# 12input.net
KiCad netlist of a schematic drawn in EAGLE
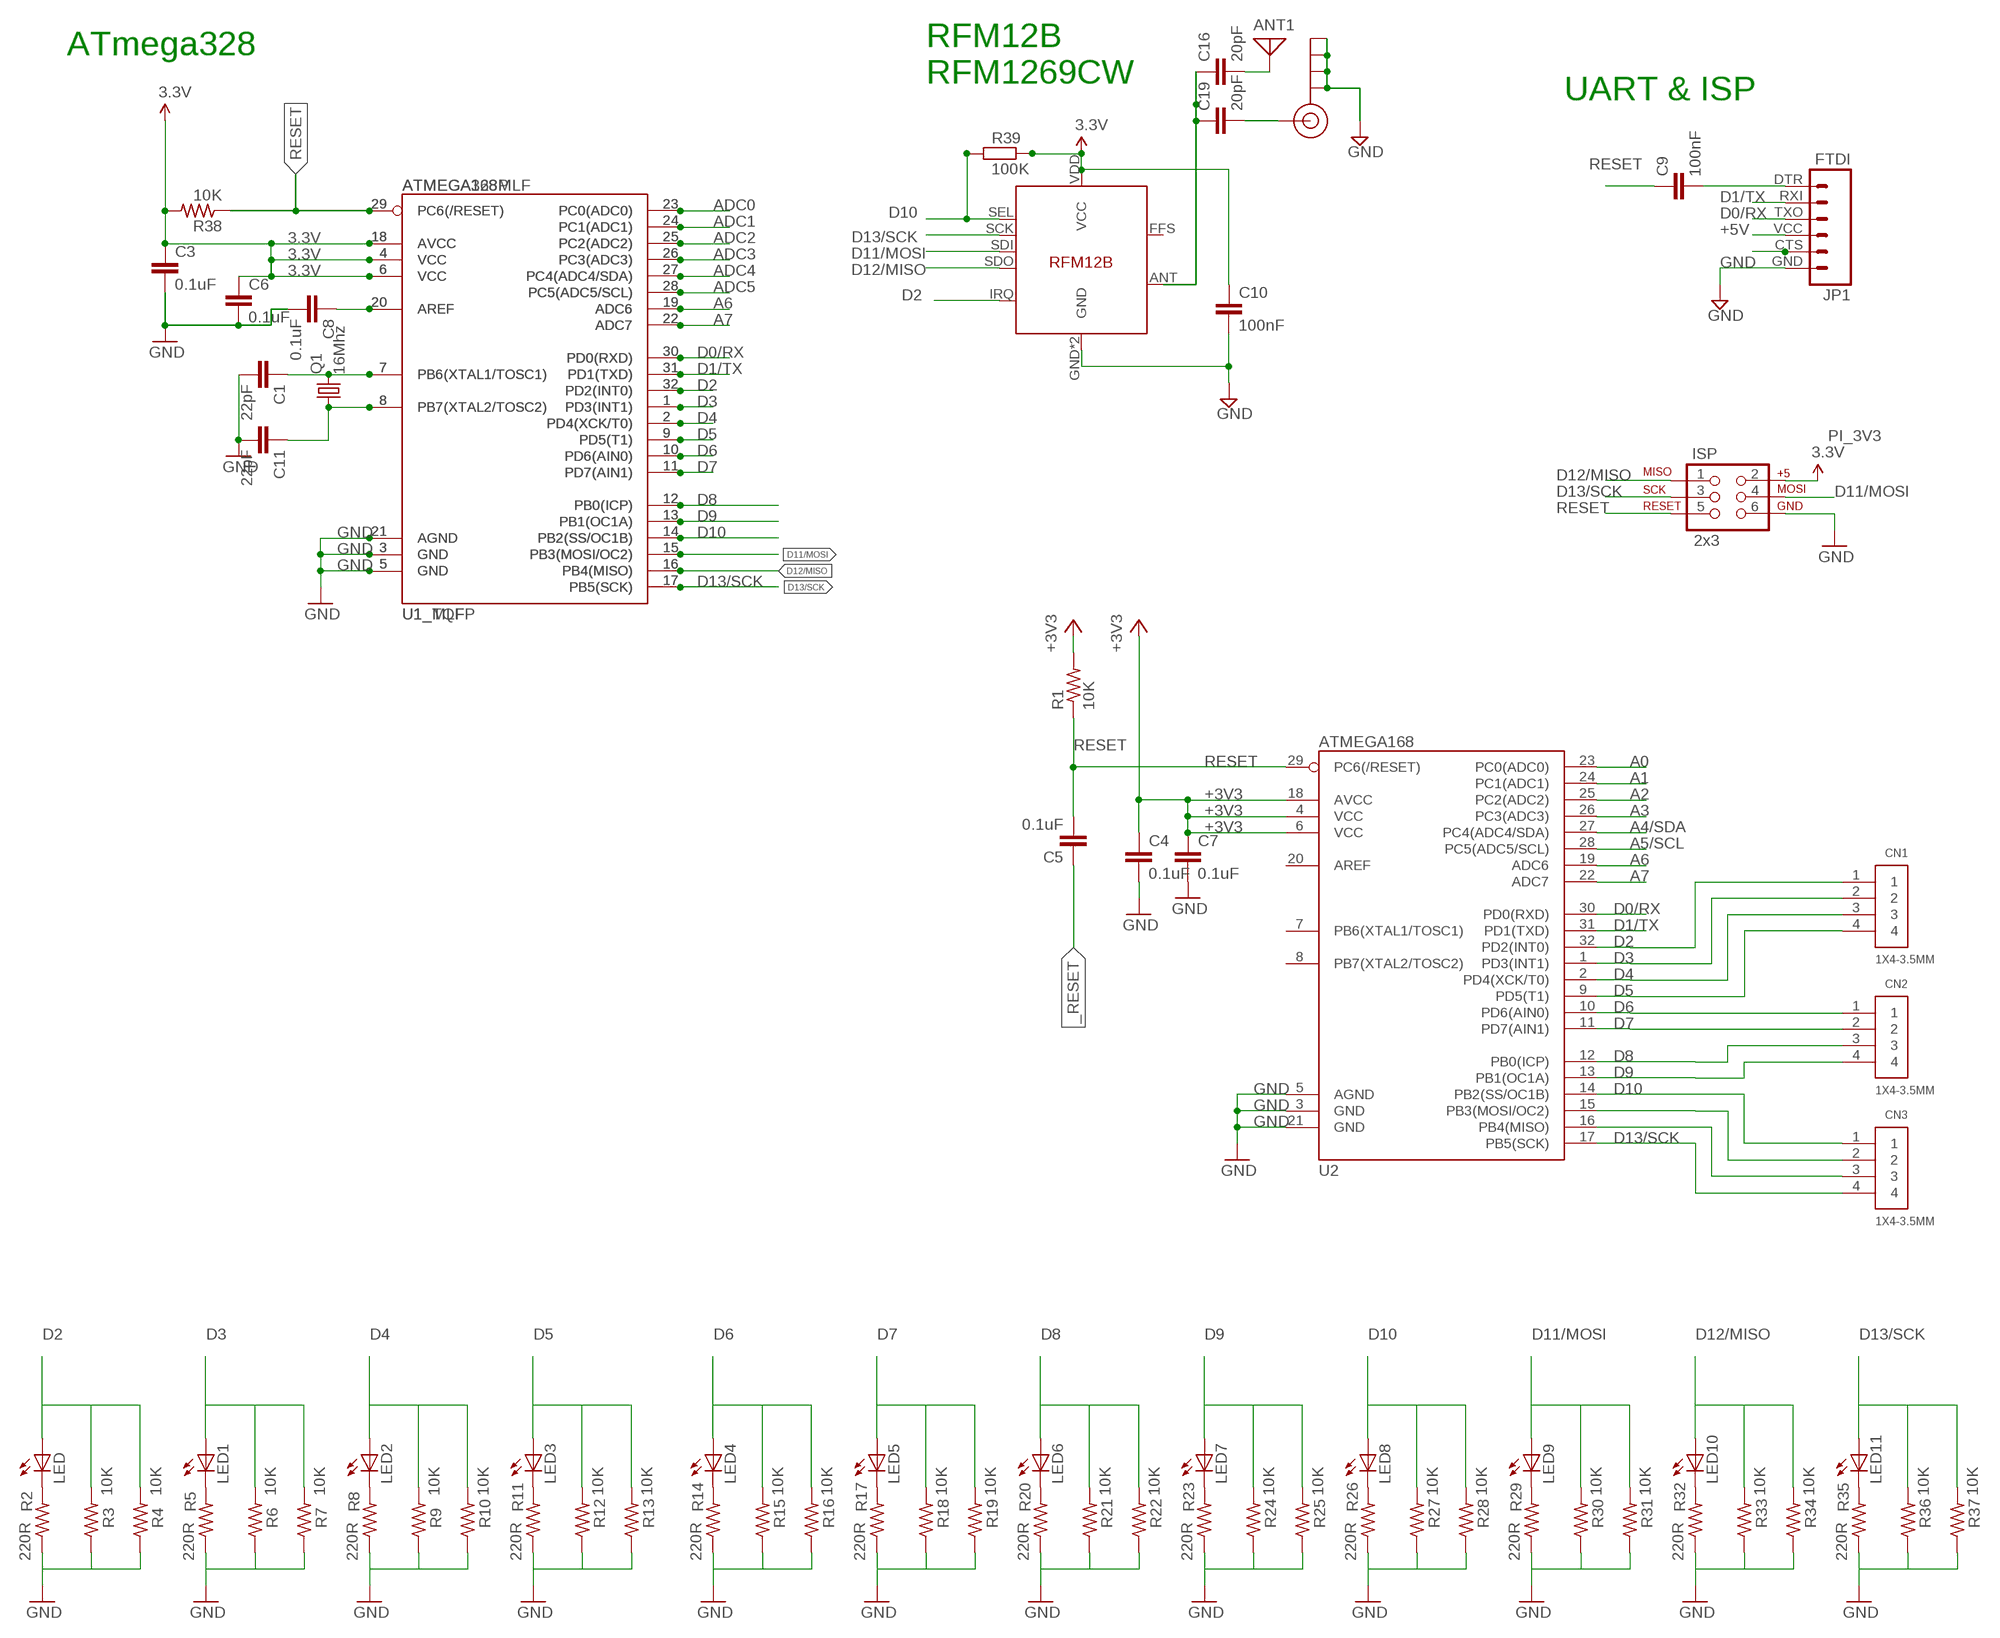
[diagram p0: schematic, sheet 1]

(export (version "E")
  (design (tool "Eeschema 10.0.6"))
  (components
    (comp (ref "ANT1")
      (value "ANTENNA")
      (footprint "eagle-import:PAD-01")
      (libsource (lib "eagle-import") (part "ANTENNA"))
    )
    (comp (ref "C1")
      (value "22pF")
      (footprint "eagle-import:C0603")
      (libsource (lib "eagle-import") (part "resistor_C-EUC0603"))
    )
    (comp (ref "C3")
      (value "0.1uF")
      (footprint "eagle-import:C0603")
      (libsource (lib "eagle-import") (part "C-EUC0603"))
    )
    (comp (ref "C4")
      (value "0.1uF")
      (footprint "eagle-import:C0603")
      (libsource (lib "eagle-import") (part "C-EUC0603"))
    )
    (comp (ref "C5")
      (value "0.1uF")
      (footprint "eagle-import:C0603")
      (libsource (lib "eagle-import") (part "C-EUC0603"))
    )
    (comp (ref "C6")
      (value "0.1uF")
      (footprint "eagle-import:C0603")
      (libsource (lib "eagle-import") (part "resistor_C-EUC0603"))
    )
    (comp (ref "C7")
      (value "0.1uF")
      (footprint "eagle-import:C0603")
      (libsource (lib "eagle-import") (part "resistor_C-EUC0603"))
    )
    (comp (ref "C8")
      (value "0.1uF")
      (footprint "eagle-import:C0603")
      (libsource (lib "eagle-import") (part "resistor_C-EUC0603"))
    )
    (comp (ref "C9")
      (value "100nF")
      (footprint "eagle-import:C0603")
      (libsource (lib "eagle-import") (part "C-EUC0603"))
    )
    (comp (ref "C10")
      (value "100nF")
      (footprint "eagle-import:C0603")
      (libsource (lib "eagle-import") (part "C-EUC0603"))
    )
    (comp (ref "C11")
      (value "22pF")
      (footprint "eagle-import:C0603")
      (libsource (lib "eagle-import") (part "resistor_C-EUC0603"))
    )
    (comp (ref "C16")
      (value "20pF")
      (footprint "eagle-import:C0603")
      (libsource (lib "eagle-import") (part "C-EUC0603"))
    )
    (comp (ref "C19")
      (value "20pF")
      (footprint "eagle-import:C0603")
      (libsource (lib "eagle-import") (part "C-EUC0603"))
    )
    (comp (ref "CN1")
      (value "1X4-3.5MM")
      (footprint "eagle-import:1X04-3.5MM")
      (libsource (lib "eagle-import") (part "1X4-3.5MM"))
    )
    (comp (ref "CN2")
      (value "1X4-3.5MM")
      (footprint "eagle-import:1X04-3.5MM")
      (libsource (lib "eagle-import") (part "1X4-3.5MM"))
    )
    (comp (ref "CN3")
      (value "1X4-3.5MM")
      (footprint "eagle-import:1X04-3.5MM")
      (libsource (lib "eagle-import") (part "1X4-3.5MM"))
    )
    (comp (ref "ISP")
      (value "2x3")
      (footprint "eagle-import:2X3")
      (libsource (lib "eagle-import") (part "AVR_SPI_PRG_6PTH"))
    )
    (comp (ref "J$1")
      (value "SMA_EDGE")
      (footprint "eagle-import:SMA-EDGE")
      (libsource (lib "eagle-import") (part "SMA_EDGE"))
    )
    (comp (ref "JP1")
      (value "FTDI")
      (footprint "eagle-import:FTDI_BASIC")
      (libsource (lib "eagle-import") (part "FTDI_BASICPTH"))
    )
    (comp (ref "LED")
      (value "LEDSML0603")
      (footprint "eagle-import:SML0603")
      (libsource (lib "eagle-import") (part "LEDSML0603"))
    )
    (comp (ref "LED1")
      (value "LEDSML0603")
      (footprint "eagle-import:SML0603")
      (libsource (lib "eagle-import") (part "LEDSML0603"))
    )
    (comp (ref "LED2")
      (value "LEDSML0603")
      (footprint "eagle-import:SML0603")
      (libsource (lib "eagle-import") (part "LEDSML0603"))
    )
    (comp (ref "LED3")
      (value "LEDSML0603")
      (footprint "eagle-import:SML0603")
      (libsource (lib "eagle-import") (part "LEDSML0603"))
    )
    (comp (ref "LED4")
      (value "LEDSML0603")
      (footprint "eagle-import:SML0603")
      (libsource (lib "eagle-import") (part "LEDSML0603"))
    )
    (comp (ref "LED5")
      (value "LEDSML0603")
      (footprint "eagle-import:SML0603")
      (libsource (lib "eagle-import") (part "LEDSML0603"))
    )
    (comp (ref "LED6")
      (value "LEDSML0603")
      (footprint "eagle-import:SML0603")
      (libsource (lib "eagle-import") (part "LEDSML0603"))
    )
    (comp (ref "LED7")
      (value "LEDSML0603")
      (footprint "eagle-import:SML0603")
      (libsource (lib "eagle-import") (part "LEDSML0603"))
    )
    (comp (ref "LED8")
      (value "LEDSML0603")
      (footprint "eagle-import:SML0603")
      (libsource (lib "eagle-import") (part "LEDSML0603"))
    )
    (comp (ref "LED9")
      (value "LEDSML0603")
      (footprint "eagle-import:SML0603")
      (libsource (lib "eagle-import") (part "LEDSML0603"))
    )
    (comp (ref "LED10")
      (value "LEDSML0603")
      (footprint "eagle-import:SML0603")
      (libsource (lib "eagle-import") (part "LEDSML0603"))
    )
    (comp (ref "LED11")
      (value "LEDSML0603")
      (footprint "eagle-import:SML0603")
      (libsource (lib "eagle-import") (part "LEDSML0603"))
    )
    (comp (ref "Q1")
      (value "16Mhz")
      (footprint "eagle-import:HC49UP")
      (libsource (lib "eagle-import") (part "CRYSTALHC49UP"))
    )
    (comp (ref "R1")
      (value "10K")
      (footprint "eagle-import:R0603")
      (libsource (lib "eagle-import") (part "R-US_R0603"))
    )
    (comp (ref "R2")
      (value "220R")
      (footprint "eagle-import:R0603")
      (libsource (lib "eagle-import") (part "R-US_R0603"))
    )
    (comp (ref "R3")
      (value "10K")
      (footprint "eagle-import:R0603")
      (libsource (lib "eagle-import") (part "R-US_R0603"))
    )
    (comp (ref "R4")
      (value "10K")
      (footprint "eagle-import:0204_7")
      (libsource (lib "eagle-import") (part "R-US_0204/7"))
    )
    (comp (ref "R5")
      (value "220R")
      (footprint "eagle-import:R0603")
      (libsource (lib "eagle-import") (part "R-US_R0603"))
    )
    (comp (ref "R6")
      (value "10K")
      (footprint "eagle-import:R0603")
      (libsource (lib "eagle-import") (part "R-US_R0603"))
    )
    (comp (ref "R7")
      (value "10K")
      (footprint "eagle-import:0204_7")
      (libsource (lib "eagle-import") (part "R-US_0204/7"))
    )
    (comp (ref "R8")
      (value "220R")
      (footprint "eagle-import:R0603")
      (libsource (lib "eagle-import") (part "R-US_R0603"))
    )
    (comp (ref "R9")
      (value "10K")
      (footprint "eagle-import:R0603")
      (libsource (lib "eagle-import") (part "R-US_R0603"))
    )
    (comp (ref "R10")
      (value "10K")
      (footprint "eagle-import:0204_7")
      (libsource (lib "eagle-import") (part "R-US_0204/7"))
    )
    (comp (ref "R11")
      (value "220R")
      (footprint "eagle-import:R0603")
      (libsource (lib "eagle-import") (part "R-US_R0603"))
    )
    (comp (ref "R12")
      (value "10K")
      (footprint "eagle-import:R0603")
      (libsource (lib "eagle-import") (part "R-US_R0603"))
    )
    (comp (ref "R13")
      (value "10K")
      (footprint "eagle-import:0204_7")
      (libsource (lib "eagle-import") (part "R-US_0204/7"))
    )
    (comp (ref "R14")
      (value "220R")
      (footprint "eagle-import:R0603")
      (libsource (lib "eagle-import") (part "R-US_R0603"))
    )
    (comp (ref "R15")
      (value "10K")
      (footprint "eagle-import:R0603")
      (libsource (lib "eagle-import") (part "R-US_R0603"))
    )
    (comp (ref "R16")
      (value "10K")
      (footprint "eagle-import:0204_7")
      (libsource (lib "eagle-import") (part "R-US_0204/7"))
    )
    (comp (ref "R17")
      (value "220R")
      (footprint "eagle-import:R0603")
      (libsource (lib "eagle-import") (part "R-US_R0603"))
    )
    (comp (ref "R18")
      (value "10K")
      (footprint "eagle-import:R0603")
      (libsource (lib "eagle-import") (part "R-US_R0603"))
    )
    (comp (ref "R19")
      (value "10K")
      (footprint "eagle-import:0204_7")
      (libsource (lib "eagle-import") (part "R-US_0204/7"))
    )
    (comp (ref "R20")
      (value "220R")
      (footprint "eagle-import:R0603")
      (libsource (lib "eagle-import") (part "R-US_R0603"))
    )
    (comp (ref "R21")
      (value "10K")
      (footprint "eagle-import:R0603")
      (libsource (lib "eagle-import") (part "R-US_R0603"))
    )
    (comp (ref "R22")
      (value "10K")
      (footprint "eagle-import:0204_7")
      (libsource (lib "eagle-import") (part "R-US_0204/7"))
    )
    (comp (ref "R23")
      (value "220R")
      (footprint "eagle-import:R0603")
      (libsource (lib "eagle-import") (part "R-US_R0603"))
    )
    (comp (ref "R24")
      (value "10K")
      (footprint "eagle-import:R0603")
      (libsource (lib "eagle-import") (part "R-US_R0603"))
    )
    (comp (ref "R25")
      (value "10K")
      (footprint "eagle-import:0204_7")
      (libsource (lib "eagle-import") (part "R-US_0204/7"))
    )
    (comp (ref "R26")
      (value "220R")
      (footprint "eagle-import:R0603")
      (libsource (lib "eagle-import") (part "R-US_R0603"))
    )
    (comp (ref "R27")
      (value "10K")
      (footprint "eagle-import:R0603")
      (libsource (lib "eagle-import") (part "R-US_R0603"))
    )
    (comp (ref "R28")
      (value "10K")
      (footprint "eagle-import:0204_7")
      (libsource (lib "eagle-import") (part "R-US_0204/7"))
    )
    (comp (ref "R29")
      (value "220R")
      (footprint "eagle-import:R0603")
      (libsource (lib "eagle-import") (part "R-US_R0603"))
    )
    (comp (ref "R30")
      (value "10K")
      (footprint "eagle-import:R0603")
      (libsource (lib "eagle-import") (part "R-US_R0603"))
    )
    (comp (ref "R31")
      (value "10K")
      (footprint "eagle-import:0204_7")
      (libsource (lib "eagle-import") (part "R-US_0204/7"))
    )
    (comp (ref "R32")
      (value "220R")
      (footprint "eagle-import:R0603")
      (libsource (lib "eagle-import") (part "R-US_R0603"))
    )
    (comp (ref "R33")
      (value "10K")
      (footprint "eagle-import:R0603")
      (libsource (lib "eagle-import") (part "R-US_R0603"))
    )
    (comp (ref "R34")
      (value "10K")
      (footprint "eagle-import:0204_7")
      (libsource (lib "eagle-import") (part "R-US_0204/7"))
    )
    (comp (ref "R35")
      (value "220R")
      (footprint "eagle-import:R0603")
      (libsource (lib "eagle-import") (part "R-US_R0603"))
    )
    (comp (ref "R36")
      (value "10K")
      (footprint "eagle-import:R0603")
      (libsource (lib "eagle-import") (part "R-US_R0603"))
    )
    (comp (ref "R37")
      (value "10K")
      (footprint "eagle-import:0204_7")
      (libsource (lib "eagle-import") (part "R-US_0204/7"))
    )
    (comp (ref "R38")
      (value "10K")
      (footprint "eagle-import:R0603")
      (libsource (lib "eagle-import") (part "R-US_R0603"))
    )
    (comp (ref "R39")
      (value "100K")
      (footprint "eagle-import:R0603")
      (libsource (lib "eagle-import") (part "R-EU_R0603"))
    )
    (comp (ref "U$14")
      (value "RFM12B")
      (footprint "eagle-import:RFM12B")
      (libsource (lib "eagle-import") (part "RFM12B"))
    )
    (comp (ref "U1_MLF")
      (value "ATMEGA168MLF")
      (footprint "eagle-import:MLF32")
      (libsource (lib "eagle-import") (part "SparkFun-DigitalIC_ATMEGA168MLF"))
    )
    (comp (ref "U1_TQFP")
      (value "ATMEGA328P")
      (footprint "eagle-import:TQFP32-08")
      (libsource (lib "eagle-import") (part "ATMEGA328_SMT"))
    )
    (comp (ref "U2")
      (value "ATMEGA168")
      (footprint "eagle-import:TQFP32-08")
      (libsource (lib "eagle-import") (part "ATMEGA168"))
    )
  )
  (nets
    (net (code "1") (name "+3V3") (class "Default")
      (node (ref "C4") (pin "1") (pinfunction "1_1") (pintype "passive"))
      (node (ref "C7") (pin "1") (pinfunction "1_1") (pintype "passive"))
      (node (ref "R1") (pin "2") (pinfunction "2_2") (pintype "passive"))
      (node (ref "U2") (pin "18") (pinfunction "AVCC_18") (pintype "bidirectional"))
      (node (ref "U2") (pin "4") (pinfunction "VCC_4") (pintype "bidirectional"))
      (node (ref "U2") (pin "6") (pinfunction "VCC_6") (pintype "bidirectional"))
    )
    (net (code "2") (name "/+5V") (class "Default")
      (node (ref "JP1") (pin "VCC") (pinfunction "4_VCC") (pintype "passive"))
    )
    (net (code "3") (name "/A0") (class "Default")
      (node (ref "U2") (pin "23") (pinfunction "PC0(ADC0)_23") (pintype "bidirectional"))
    )
    (net (code "4") (name "/A1") (class "Default")
      (node (ref "U2") (pin "24") (pinfunction "PC1(ADC1)_24") (pintype "bidirectional"))
    )
    (net (code "5") (name "/A2") (class "Default")
      (node (ref "U2") (pin "25") (pinfunction "PC2(ADC2)_25") (pintype "bidirectional"))
    )
    (net (code "6") (name "/A3") (class "Default")
      (node (ref "U2") (pin "26") (pinfunction "PC3(ADC3)_26") (pintype "bidirectional"))
    )
    (net (code "7") (name "/A4{slash}SDA") (class "Default")
      (node (ref "U2") (pin "27") (pinfunction "PC4(ADC4/SDA)_27") (pintype "bidirectional"))
    )
    (net (code "8") (name "/A5{slash}SCL") (class "Default")
      (node (ref "U2") (pin "28") (pinfunction "PC5(ADC5/SCL)_28") (pintype "bidirectional"))
    )
    (net (code "9") (name "/A6") (class "Default")
      (node (ref "U1_MLF") (pin "19") (pinfunction "ADC6_19") (pintype "bidirectional"))
      (node (ref "U1_TQFP") (pin "19") (pinfunction "ADC6_19") (pintype "bidirectional"))
      (node (ref "U2") (pin "19") (pinfunction "ADC6_19") (pintype "bidirectional"))
    )
    (net (code "10") (name "/A7") (class "Default")
      (node (ref "U1_MLF") (pin "22") (pinfunction "ADC7_22") (pintype "bidirectional"))
      (node (ref "U1_TQFP") (pin "22") (pinfunction "ADC7_22") (pintype "bidirectional"))
      (node (ref "U2") (pin "22") (pinfunction "ADC7_22") (pintype "bidirectional"))
    )
    (net (code "11") (name "/ADC0") (class "Default")
      (node (ref "U1_MLF") (pin "23") (pinfunction "PC0(ADC0)_23") (pintype "bidirectional"))
      (node (ref "U1_TQFP") (pin "23") (pinfunction "PC0(ADC0)_23") (pintype "bidirectional"))
    )
    (net (code "12") (name "/ADC1") (class "Default")
      (node (ref "U1_MLF") (pin "24") (pinfunction "PC1(ADC1)_24") (pintype "bidirectional"))
      (node (ref "U1_TQFP") (pin "24") (pinfunction "PC1(ADC1)_24") (pintype "bidirectional"))
    )
    (net (code "13") (name "/ADC2") (class "Default")
      (node (ref "U1_MLF") (pin "25") (pinfunction "PC2(ADC2)_25") (pintype "bidirectional"))
      (node (ref "U1_TQFP") (pin "25") (pinfunction "PC2(ADC2)_25") (pintype "bidirectional"))
    )
    (net (code "14") (name "/ADC3") (class "Default")
      (node (ref "U1_MLF") (pin "26") (pinfunction "PC3(ADC3)_26") (pintype "bidirectional"))
      (node (ref "U1_TQFP") (pin "26") (pinfunction "PC3(ADC3)_26") (pintype "bidirectional"))
    )
    (net (code "15") (name "/ADC4") (class "Default")
      (node (ref "U1_MLF") (pin "27") (pinfunction "PC4(ADC4/SDA)_27") (pintype "bidirectional"))
      (node (ref "U1_TQFP") (pin "27") (pinfunction "PC4(ADC4/SDA)_27") (pintype "bidirectional"))
    )
    (net (code "16") (name "/ADC5") (class "Default")
      (node (ref "U1_MLF") (pin "28") (pinfunction "PC5(ADC5/SCL)_28") (pintype "bidirectional"))
      (node (ref "U1_TQFP") (pin "28") (pinfunction "PC5(ADC5/SCL)_28") (pintype "bidirectional"))
    )
    (net (code "17") (name "/D0{slash}RX") (class "Default")
      (node (ref "JP1") (pin "TXO") (pinfunction "3_TXO") (pintype "passive"))
      (node (ref "U1_MLF") (pin "30") (pinfunction "PD0(RXD)_30") (pintype "bidirectional"))
      (node (ref "U1_TQFP") (pin "30") (pinfunction "PD0(RXD)_30") (pintype "bidirectional"))
      (node (ref "U2") (pin "30") (pinfunction "PD0(RXD)_30") (pintype "bidirectional"))
    )
    (net (code "18") (name "/D1{slash}TX") (class "Default")
      (node (ref "JP1") (pin "RXI") (pinfunction "2_RXI") (pintype "passive"))
      (node (ref "U1_MLF") (pin "31") (pinfunction "PD1(TXD)_31") (pintype "bidirectional"))
      (node (ref "U1_TQFP") (pin "31") (pinfunction "PD1(TXD)_31") (pintype "bidirectional"))
      (node (ref "U2") (pin "31") (pinfunction "PD1(TXD)_31") (pintype "bidirectional"))
    )
    (net (code "19") (name "/D2") (class "Default")
      (node (ref "CN1") (pin "1") (pinfunction "1_1") (pintype "bidirectional"))
      (node (ref "LED") (pin "A") (pinfunction "A_A") (pintype "passive"))
      (node (ref "R3") (pin "2") (pinfunction "2_2") (pintype "passive"))
      (node (ref "R4") (pin "2") (pinfunction "2_2") (pintype "passive"))
      (node (ref "U$14") (pin "IRQ") (pinfunction "IRQ_IRQ") (pintype "open_collector"))
      (node (ref "U1_MLF") (pin "32") (pinfunction "PD2(INT0)_32") (pintype "bidirectional"))
      (node (ref "U1_TQFP") (pin "32") (pinfunction "PD2(INT0)_32") (pintype "bidirectional"))
      (node (ref "U2") (pin "32") (pinfunction "PD2(INT0)_32") (pintype "bidirectional"))
    )
    (net (code "20") (name "/D3") (class "Default")
      (node (ref "CN1") (pin "2") (pinfunction "2_2") (pintype "bidirectional"))
      (node (ref "LED1") (pin "A") (pinfunction "A_A") (pintype "passive"))
      (node (ref "R6") (pin "2") (pinfunction "2_2") (pintype "passive"))
      (node (ref "R7") (pin "2") (pinfunction "2_2") (pintype "passive"))
      (node (ref "U1_MLF") (pin "1") (pinfunction "PD3(INT1)_1") (pintype "bidirectional"))
      (node (ref "U1_TQFP") (pin "1") (pinfunction "PD3(INT1)_1") (pintype "bidirectional"))
      (node (ref "U2") (pin "1") (pinfunction "PD3(INT1)_1") (pintype "bidirectional"))
    )
    (net (code "21") (name "/D4") (class "Default")
      (node (ref "CN1") (pin "3") (pinfunction "3_3") (pintype "bidirectional"))
      (node (ref "LED2") (pin "A") (pinfunction "A_A") (pintype "passive"))
      (node (ref "R10") (pin "2") (pinfunction "2_2") (pintype "passive"))
      (node (ref "R9") (pin "2") (pinfunction "2_2") (pintype "passive"))
      (node (ref "U1_MLF") (pin "2") (pinfunction "PD4(XCK/T0)_2") (pintype "bidirectional"))
      (node (ref "U1_TQFP") (pin "2") (pinfunction "PD4(XCK/T0)_2") (pintype "bidirectional"))
      (node (ref "U2") (pin "2") (pinfunction "PD4(XCK/T0)_2") (pintype "bidirectional"))
    )
    (net (code "22") (name "/D5") (class "Default")
      (node (ref "CN1") (pin "4") (pinfunction "4_4") (pintype "bidirectional"))
      (node (ref "LED3") (pin "A") (pinfunction "A_A") (pintype "passive"))
      (node (ref "R12") (pin "2") (pinfunction "2_2") (pintype "passive"))
      (node (ref "R13") (pin "2") (pinfunction "2_2") (pintype "passive"))
      (node (ref "U1_MLF") (pin "9") (pinfunction "PD5(T1)_9") (pintype "bidirectional"))
      (node (ref "U1_TQFP") (pin "9") (pinfunction "PD5(T1)_9") (pintype "bidirectional"))
      (node (ref "U2") (pin "9") (pinfunction "PD5(T1)_9") (pintype "bidirectional"))
    )
    (net (code "23") (name "/D6") (class "Default")
      (node (ref "CN2") (pin "1") (pinfunction "1_1") (pintype "bidirectional"))
      (node (ref "LED4") (pin "A") (pinfunction "A_A") (pintype "passive"))
      (node (ref "R15") (pin "2") (pinfunction "2_2") (pintype "passive"))
      (node (ref "R16") (pin "2") (pinfunction "2_2") (pintype "passive"))
      (node (ref "U1_MLF") (pin "10") (pinfunction "PD6(AIN0)_10") (pintype "bidirectional"))
      (node (ref "U1_TQFP") (pin "10") (pinfunction "PD6(AIN0)_10") (pintype "bidirectional"))
      (node (ref "U2") (pin "10") (pinfunction "PD6(AIN0)_10") (pintype "bidirectional"))
    )
    (net (code "24") (name "/D7") (class "Default")
      (node (ref "CN2") (pin "2") (pinfunction "2_2") (pintype "bidirectional"))
      (node (ref "LED5") (pin "A") (pinfunction "A_A") (pintype "passive"))
      (node (ref "R18") (pin "2") (pinfunction "2_2") (pintype "passive"))
      (node (ref "R19") (pin "2") (pinfunction "2_2") (pintype "passive"))
      (node (ref "U1_MLF") (pin "11") (pinfunction "PD7(AIN1)_11") (pintype "bidirectional"))
      (node (ref "U1_TQFP") (pin "11") (pinfunction "PD7(AIN1)_11") (pintype "bidirectional"))
      (node (ref "U2") (pin "11") (pinfunction "PD7(AIN1)_11") (pintype "bidirectional"))
    )
    (net (code "25") (name "/D8") (class "Default")
      (node (ref "CN2") (pin "3") (pinfunction "3_3") (pintype "bidirectional"))
      (node (ref "LED6") (pin "A") (pinfunction "A_A") (pintype "passive"))
      (node (ref "R21") (pin "2") (pinfunction "2_2") (pintype "passive"))
      (node (ref "R22") (pin "2") (pinfunction "2_2") (pintype "passive"))
      (node (ref "U1_MLF") (pin "12") (pinfunction "PB0(ICP)_12") (pintype "bidirectional"))
      (node (ref "U1_TQFP") (pin "12") (pinfunction "PB0(ICP)_12") (pintype "bidirectional"))
      (node (ref "U2") (pin "12") (pinfunction "PB0(ICP)_12") (pintype "bidirectional"))
    )
    (net (code "26") (name "/D9") (class "Default")
      (node (ref "CN2") (pin "4") (pinfunction "4_4") (pintype "bidirectional"))
      (node (ref "LED7") (pin "A") (pinfunction "A_A") (pintype "passive"))
      (node (ref "R24") (pin "2") (pinfunction "2_2") (pintype "passive"))
      (node (ref "R25") (pin "2") (pinfunction "2_2") (pintype "passive"))
      (node (ref "U1_MLF") (pin "13") (pinfunction "PB1(OC1A)_13") (pintype "bidirectional"))
      (node (ref "U1_TQFP") (pin "13") (pinfunction "PB1(OC1A)_13") (pintype "bidirectional"))
      (node (ref "U2") (pin "13") (pinfunction "PB1(OC1A)_13") (pintype "bidirectional"))
    )
    (net (code "27") (name "/D10") (class "Default")
      (node (ref "CN3") (pin "1") (pinfunction "1_1") (pintype "bidirectional"))
      (node (ref "LED8") (pin "A") (pinfunction "A_A") (pintype "passive"))
      (node (ref "R27") (pin "2") (pinfunction "2_2") (pintype "passive"))
      (node (ref "R28") (pin "2") (pinfunction "2_2") (pintype "passive"))
      (node (ref "R39") (pin "1") (pinfunction "1_1") (pintype "passive"))
      (node (ref "U$14") (pin "SEL") (pinfunction "SEL_SEL") (pintype "input"))
      (node (ref "U1_MLF") (pin "14") (pinfunction "PB2(SS/OC1B)_14") (pintype "bidirectional"))
      (node (ref "U1_TQFP") (pin "14") (pinfunction "PB2(SS/OC1B)_14") (pintype "bidirectional"))
      (node (ref "U2") (pin "14") (pinfunction "PB2(SS/OC1B)_14") (pintype "bidirectional"))
    )
    (net (code "29") (name "3.3V") (class "Default")
      (node (ref "C10") (pin "1") (pinfunction "1_1") (pintype "passive"))
      (node (ref "C3") (pin "1") (pinfunction "1_1") (pintype "passive"))
      (node (ref "C6") (pin "1") (pinfunction "1_1") (pintype "passive"))
      (node (ref "ISP") (pin "2") (pinfunction "2_2") (pintype "passive"))
      (node (ref "R38") (pin "2") (pinfunction "2_2") (pintype "passive"))
      (node (ref "R39") (pin "2") (pinfunction "2_2") (pintype "passive"))
      (node (ref "U$14") (pin "VDD") (pinfunction "VCC_VDD") (pintype "power_in"))
      (node (ref "U1_MLF") (pin "18") (pinfunction "AVCC_18") (pintype "bidirectional"))
      (node (ref "U1_MLF") (pin "4") (pinfunction "VCC_4") (pintype "bidirectional"))
      (node (ref "U1_MLF") (pin "6") (pinfunction "VCC_6") (pintype "bidirectional"))
      (node (ref "U1_TQFP") (pin "18") (pinfunction "AVCC_18") (pintype "bidirectional"))
      (node (ref "U1_TQFP") (pin "4") (pinfunction "VCC_4") (pintype "bidirectional"))
      (node (ref "U1_TQFP") (pin "6") (pinfunction "VCC_6") (pintype "bidirectional"))
    )
    (net (code "30") (name "D11{slash}MOSI") (class "Default")
      (node (ref "CN3") (pin "2") (pinfunction "2_2") (pintype "bidirectional"))
      (node (ref "ISP") (pin "4") (pinfunction "4_4") (pintype "passive"))
      (node (ref "LED9") (pin "A") (pinfunction "A_A") (pintype "passive"))
      (node (ref "R30") (pin "2") (pinfunction "2_2") (pintype "passive"))
      (node (ref "R31") (pin "2") (pinfunction "2_2") (pintype "passive"))
      (node (ref "U$14") (pin "SDI") (pinfunction "SDI_SDI") (pintype "input"))
      (node (ref "U1_MLF") (pin "15") (pinfunction "PB3(MOSI/OC2)_15") (pintype "bidirectional"))
      (node (ref "U1_TQFP") (pin "15") (pinfunction "PB3(MOSI/OC2)_15") (pintype "bidirectional"))
      (node (ref "U2") (pin "15") (pinfunction "PB3(MOSI/OC2)_15") (pintype "bidirectional"))
    )
    (net (code "31") (name "D12{slash}MISO") (class "Default")
      (node (ref "CN3") (pin "3") (pinfunction "3_3") (pintype "bidirectional"))
      (node (ref "ISP") (pin "1") (pinfunction "1_1") (pintype "passive"))
      (node (ref "LED10") (pin "A") (pinfunction "A_A") (pintype "passive"))
      (node (ref "R33") (pin "2") (pinfunction "2_2") (pintype "passive"))
      (node (ref "R34") (pin "2") (pinfunction "2_2") (pintype "passive"))
      (node (ref "U$14") (pin "SDO") (pinfunction "SDO_SDO") (pintype "output"))
      (node (ref "U1_MLF") (pin "16") (pinfunction "PB4(MISO)_16") (pintype "bidirectional"))
      (node (ref "U1_TQFP") (pin "16") (pinfunction "PB4(MISO)_16") (pintype "bidirectional"))
      (node (ref "U2") (pin "16") (pinfunction "PB4(MISO)_16") (pintype "bidirectional"))
    )
    (net (code "32") (name "D13{slash}SCK") (class "Default")
      (node (ref "CN3") (pin "4") (pinfunction "4_4") (pintype "bidirectional"))
      (node (ref "ISP") (pin "3") (pinfunction "3_3") (pintype "passive"))
      (node (ref "LED11") (pin "A") (pinfunction "A_A") (pintype "passive"))
      (node (ref "R36") (pin "2") (pinfunction "2_2") (pintype "passive"))
      (node (ref "R37") (pin "2") (pinfunction "2_2") (pintype "passive"))
      (node (ref "U$14") (pin "SCK") (pinfunction "SCK_SCK") (pintype "input"))
      (node (ref "U1_MLF") (pin "17") (pinfunction "PB5(SCK)_17") (pintype "bidirectional"))
      (node (ref "U1_TQFP") (pin "17") (pinfunction "PB5(SCK)_17") (pintype "bidirectional"))
      (node (ref "U2") (pin "17") (pinfunction "PB5(SCK)_17") (pintype "bidirectional"))
    )
    (net (code "33") (name "GND") (class "Default")
      (node (ref "C1") (pin "2") (pinfunction "2_2") (pintype "passive"))
      (node (ref "C10") (pin "2") (pinfunction "2_2") (pintype "passive"))
      (node (ref "C11") (pin "2") (pinfunction "2_2") (pintype "passive"))
      (node (ref "C3") (pin "2") (pinfunction "2_2") (pintype "passive"))
      (node (ref "C4") (pin "2") (pinfunction "2_2") (pintype "passive"))
      (node (ref "C6") (pin "2") (pinfunction "2_2") (pintype "passive"))
      (node (ref "C7") (pin "2") (pinfunction "2_2") (pintype "passive"))
      (node (ref "C8") (pin "2") (pinfunction "2_2") (pintype "passive"))
      (node (ref "ISP") (pin "6") (pinfunction "6_6") (pintype "passive"))
      (node (ref "J$1") (pin "GND@0") (pinfunction "GND_GND@0") (pintype "bidirectional"))
      (node (ref "J$1") (pin "GND@1") (pinfunction "GND_GND@1") (pintype "bidirectional"))
      (node (ref "J$1") (pin "GND@2") (pinfunction "GND_GND@2") (pintype "bidirectional"))
      (node (ref "J$1") (pin "GND@3") (pinfunction "GND_GND@3") (pintype "bidirectional"))
      (node (ref "JP1") (pin "GND") (pinfunction "6_GND") (pintype "passive"))
      (node (ref "R10") (pin "1") (pinfunction "1_1") (pintype "passive"))
      (node (ref "R11") (pin "1") (pinfunction "1_1") (pintype "passive"))
      (node (ref "R12") (pin "1") (pinfunction "1_1") (pintype "passive"))
      (node (ref "R13") (pin "1") (pinfunction "1_1") (pintype "passive"))
      (node (ref "R14") (pin "1") (pinfunction "1_1") (pintype "passive"))
      (node (ref "R15") (pin "1") (pinfunction "1_1") (pintype "passive"))
      (node (ref "R16") (pin "1") (pinfunction "1_1") (pintype "passive"))
      (node (ref "R17") (pin "1") (pinfunction "1_1") (pintype "passive"))
      (node (ref "R18") (pin "1") (pinfunction "1_1") (pintype "passive"))
      (node (ref "R19") (pin "1") (pinfunction "1_1") (pintype "passive"))
      (node (ref "R2") (pin "1") (pinfunction "1_1") (pintype "passive"))
      (node (ref "R20") (pin "1") (pinfunction "1_1") (pintype "passive"))
      (node (ref "R21") (pin "1") (pinfunction "1_1") (pintype "passive"))
      (node (ref "R22") (pin "1") (pinfunction "1_1") (pintype "passive"))
      (node (ref "R23") (pin "1") (pinfunction "1_1") (pintype "passive"))
      (node (ref "R24") (pin "1") (pinfunction "1_1") (pintype "passive"))
      (node (ref "R25") (pin "1") (pinfunction "1_1") (pintype "passive"))
      (node (ref "R26") (pin "1") (pinfunction "1_1") (pintype "passive"))
      (node (ref "R27") (pin "1") (pinfunction "1_1") (pintype "passive"))
      (node (ref "R28") (pin "1") (pinfunction "1_1") (pintype "passive"))
      (node (ref "R29") (pin "1") (pinfunction "1_1") (pintype "passive"))
      (node (ref "R3") (pin "1") (pinfunction "1_1") (pintype "passive"))
      (node (ref "R30") (pin "1") (pinfunction "1_1") (pintype "passive"))
      (node (ref "R31") (pin "1") (pinfunction "1_1") (pintype "passive"))
      (node (ref "R32") (pin "1") (pinfunction "1_1") (pintype "passive"))
      (node (ref "R33") (pin "1") (pinfunction "1_1") (pintype "passive"))
      (node (ref "R34") (pin "1") (pinfunction "1_1") (pintype "passive"))
      (node (ref "R35") (pin "1") (pinfunction "1_1") (pintype "passive"))
      (node (ref "R36") (pin "1") (pinfunction "1_1") (pintype "passive"))
      (node (ref "R37") (pin "1") (pinfunction "1_1") (pintype "passive"))
      (node (ref "R4") (pin "1") (pinfunction "1_1") (pintype "passive"))
      (node (ref "R5") (pin "1") (pinfunction "1_1") (pintype "passive"))
      (node (ref "R6") (pin "1") (pinfunction "1_1") (pintype "passive"))
      (node (ref "R7") (pin "1") (pinfunction "1_1") (pintype "passive"))
      (node (ref "R8") (pin "1") (pinfunction "1_1") (pintype "passive"))
      (node (ref "R9") (pin "1") (pinfunction "1_1") (pintype "passive"))
      (node (ref "U$14") (pin "GND") (pinfunction "GND_GND") (pintype "power_in"))
      (node (ref "U$14") (pin "P$12") (pinfunction "GND_P$12") (pintype "power_in"))
      (node (ref "U1_MLF") (pin "21") (pinfunction "AGND_21") (pintype "bidirectional"))
      (node (ref "U1_MLF") (pin "3") (pinfunction "GND_3") (pintype "bidirectional"))
      (node (ref "U1_MLF") (pin "5") (pinfunction "GND_5") (pintype "bidirectional"))
      (node (ref "U1_TQFP") (pin "21") (pinfunction "AGND_21") (pintype "bidirectional"))
      (node (ref "U1_TQFP") (pin "3") (pinfunction "GND_3") (pintype "bidirectional"))
      (node (ref "U1_TQFP") (pin "5") (pinfunction "GND_5") (pintype "bidirectional"))
      (node (ref "U2") (pin "21") (pinfunction "GND_21") (pintype "bidirectional"))
      (node (ref "U2") (pin "3") (pinfunction "GND_3") (pintype "bidirectional"))
      (node (ref "U2") (pin "5") (pinfunction "AGND_5") (pintype "bidirectional"))
    )
    (net (code "34") (name "Net-(ANT1-Pad1)") (class "Default")
      (node (ref "ANT1") (pin "1") (pinfunction "1_1") (pintype "output"))
      (node (ref "C16") (pin "2") (pinfunction "2_2") (pintype "passive"))
    )
    (net (code "35") (name "Net-(C16-Pad1)") (class "Default")
      (node (ref "C16") (pin "1") (pinfunction "1_1") (pintype "passive"))
      (node (ref "C19") (pin "1") (pinfunction "1_1") (pintype "passive"))
      (node (ref "U$14") (pin "ANT") (pinfunction "ANT_ANT") (pintype "passive"))
    )
    (net (code "36") (name "Net-(J$1-SIGNAL)") (class "Default")
      (node (ref "C19") (pin "2") (pinfunction "2_2") (pintype "passive"))
      (node (ref "J$1") (pin "SIG") (pinfunction "SIGNAL_SIG") (pintype "bidirectional"))
    )
    (net (code "37") (name "Net-(JP1-1)") (class "Default")
      (node (ref "C9") (pin "2") (pinfunction "2_2") (pintype "passive"))
      (node (ref "JP1") (pin "DTR") (pinfunction "1_DTR") (pintype "passive"))
    )
    (net (code "38") (name "Net-(LED-PadC)") (class "Default")
      (node (ref "LED") (pin "C") (pinfunction "C_C") (pintype "passive"))
      (node (ref "R2") (pin "2") (pinfunction "2_2") (pintype "passive"))
    )
    (net (code "39") (name "Net-(LED1-PadC)") (class "Default")
      (node (ref "LED1") (pin "C") (pinfunction "C_C") (pintype "passive"))
      (node (ref "R5") (pin "2") (pinfunction "2_2") (pintype "passive"))
    )
    (net (code "40") (name "Net-(LED2-PadC)") (class "Default")
      (node (ref "LED2") (pin "C") (pinfunction "C_C") (pintype "passive"))
      (node (ref "R8") (pin "2") (pinfunction "2_2") (pintype "passive"))
    )
    (net (code "41") (name "Net-(LED3-PadC)") (class "Default")
      (node (ref "LED3") (pin "C") (pinfunction "C_C") (pintype "passive"))
      (node (ref "R11") (pin "2") (pinfunction "2_2") (pintype "passive"))
    )
    (net (code "42") (name "Net-(LED4-PadC)") (class "Default")
      (node (ref "LED4") (pin "C") (pinfunction "C_C") (pintype "passive"))
      (node (ref "R14") (pin "2") (pinfunction "2_2") (pintype "passive"))
    )
    (net (code "43") (name "Net-(LED5-PadC)") (class "Default")
      (node (ref "LED5") (pin "C") (pinfunction "C_C") (pintype "passive"))
      (node (ref "R17") (pin "2") (pinfunction "2_2") (pintype "passive"))
    )
    (net (code "44") (name "Net-(LED6-PadC)") (class "Default")
      (node (ref "LED6") (pin "C") (pinfunction "C_C") (pintype "passive"))
      (node (ref "R20") (pin "2") (pinfunction "2_2") (pintype "passive"))
    )
    (net (code "45") (name "Net-(LED7-PadC)") (class "Default")
      (node (ref "LED7") (pin "C") (pinfunction "C_C") (pintype "passive"))
      (node (ref "R23") (pin "2") (pinfunction "2_2") (pintype "passive"))
    )
    (net (code "46") (name "Net-(LED8-PadC)") (class "Default")
      (node (ref "LED8") (pin "C") (pinfunction "C_C") (pintype "passive"))
      (node (ref "R26") (pin "2") (pinfunction "2_2") (pintype "passive"))
    )
    (net (code "47") (name "Net-(LED9-PadC)") (class "Default")
      (node (ref "LED9") (pin "C") (pinfunction "C_C") (pintype "passive"))
      (node (ref "R29") (pin "2") (pinfunction "2_2") (pintype "passive"))
    )
    (net (code "48") (name "Net-(LED10-PadC)") (class "Default")
      (node (ref "LED10") (pin "C") (pinfunction "C_C") (pintype "passive"))
      (node (ref "R32") (pin "2") (pinfunction "2_2") (pintype "passive"))
    )
    (net (code "49") (name "Net-(LED11-PadC)") (class "Default")
      (node (ref "LED11") (pin "C") (pinfunction "C_C") (pintype "passive"))
      (node (ref "R35") (pin "2") (pinfunction "2_2") (pintype "passive"))
    )
    (net (code "50") (name "Net-(U1_MLF-AREF)") (class "Default")
      (node (ref "C8") (pin "1") (pinfunction "1_1") (pintype "passive"))
      (node (ref "U1_MLF") (pin "20") (pinfunction "AREF_20") (pintype "bidirectional"))
      (node (ref "U1_TQFP") (pin "20") (pinfunction "AREF_20") (pintype "bidirectional"))
    )
    (net (code "51") (name "Net-(U1_MLF-PB6(XTAL1{slash}TOSC1))") (class "Default")
      (node (ref "C1") (pin "1") (pinfunction "1_1") (pintype "passive"))
      (node (ref "Q1") (pin "2") (pinfunction "2_2") (pintype "passive"))
      (node (ref "U1_MLF") (pin "7") (pinfunction "PB6(XTAL1/TOSC1)_7") (pintype "bidirectional"))
      (node (ref "U1_TQFP") (pin "7") (pinfunction "PB6(XTAL1/TOSC1)_7") (pintype "bidirectional"))
    )
    (net (code "52") (name "Net-(U1_MLF-PB7(XTAL2{slash}TOSC2))") (class "Default")
      (node (ref "C11") (pin "1") (pinfunction "1_1") (pintype "passive"))
      (node (ref "Q1") (pin "1") (pinfunction "1_1") (pintype "passive"))
      (node (ref "U1_MLF") (pin "8") (pinfunction "PB7(XTAL2/TOSC2)_8") (pintype "bidirectional"))
      (node (ref "U1_TQFP") (pin "8") (pinfunction "PB7(XTAL2/TOSC2)_8") (pintype "bidirectional"))
    )
    (net (code "53") (name "RESET") (class "Default")
      (node (ref "C5") (pin "2") (pinfunction "2_2") (pintype "passive"))
      (node (ref "C9") (pin "1") (pinfunction "1_1") (pintype "passive"))
      (node (ref "ISP") (pin "5") (pinfunction "5_5") (pintype "passive"))
      (node (ref "R1") (pin "1") (pinfunction "1_1") (pintype "passive"))
      (node (ref "R38") (pin "1") (pinfunction "1_1") (pintype "passive"))
      (node (ref "U1_MLF") (pin "29") (pinfunction "PC6(/RESET)_29") (pintype "bidirectional"))
      (node (ref "U1_TQFP") (pin "29") (pinfunction "PC6(/RESET)_29") (pintype "bidirectional"))
      (node (ref "U2") (pin "29") (pinfunction "PC6(/RESET)_29") (pintype "bidirectional"))
    )
    (net (code "54") (name "_RESET") (class "Default")
      (node (ref "C5") (pin "1") (pinfunction "1_1") (pintype "passive"))
    )
    (net (code "55") (name "unconnected-(JP1-5-PadCTS)") (class "Default")
      (node (ref "JP1") (pin "CTS") (pinfunction "5_CTS") (pintype "passive"))
    )
    (net (code "56") (name "unconnected-(U$14-PadFFS)") (class "Default")
      (node (ref "U$14") (pin "FFS") (pinfunction "FFS_FFS") (pintype "bidirectional"))
    )
    (net (code "57") (name "unconnected-(U2-AREF-Pad20)") (class "Default")
      (node (ref "U2") (pin "20") (pinfunction "AREF_20") (pintype "bidirectional"))
    )
    (net (code "58") (name "unconnected-(U2-PB6(XTAL1{slash}TOSC1)-Pad7)") (class "Default")
      (node (ref "U2") (pin "7") (pinfunction "PB6(XTAL1/TOSC1)_7") (pintype "bidirectional"))
    )
    (net (code "59") (name "unconnected-(U2-PB7(XTAL2{slash}TOSC2)-Pad8)") (class "Default")
      (node (ref "U2") (pin "8") (pinfunction "PB7(XTAL2/TOSC2)_8") (pintype "bidirectional"))
    )
  )
)
